# fmc.net
KiCad netlist of a schematic drawn in Altium Designer
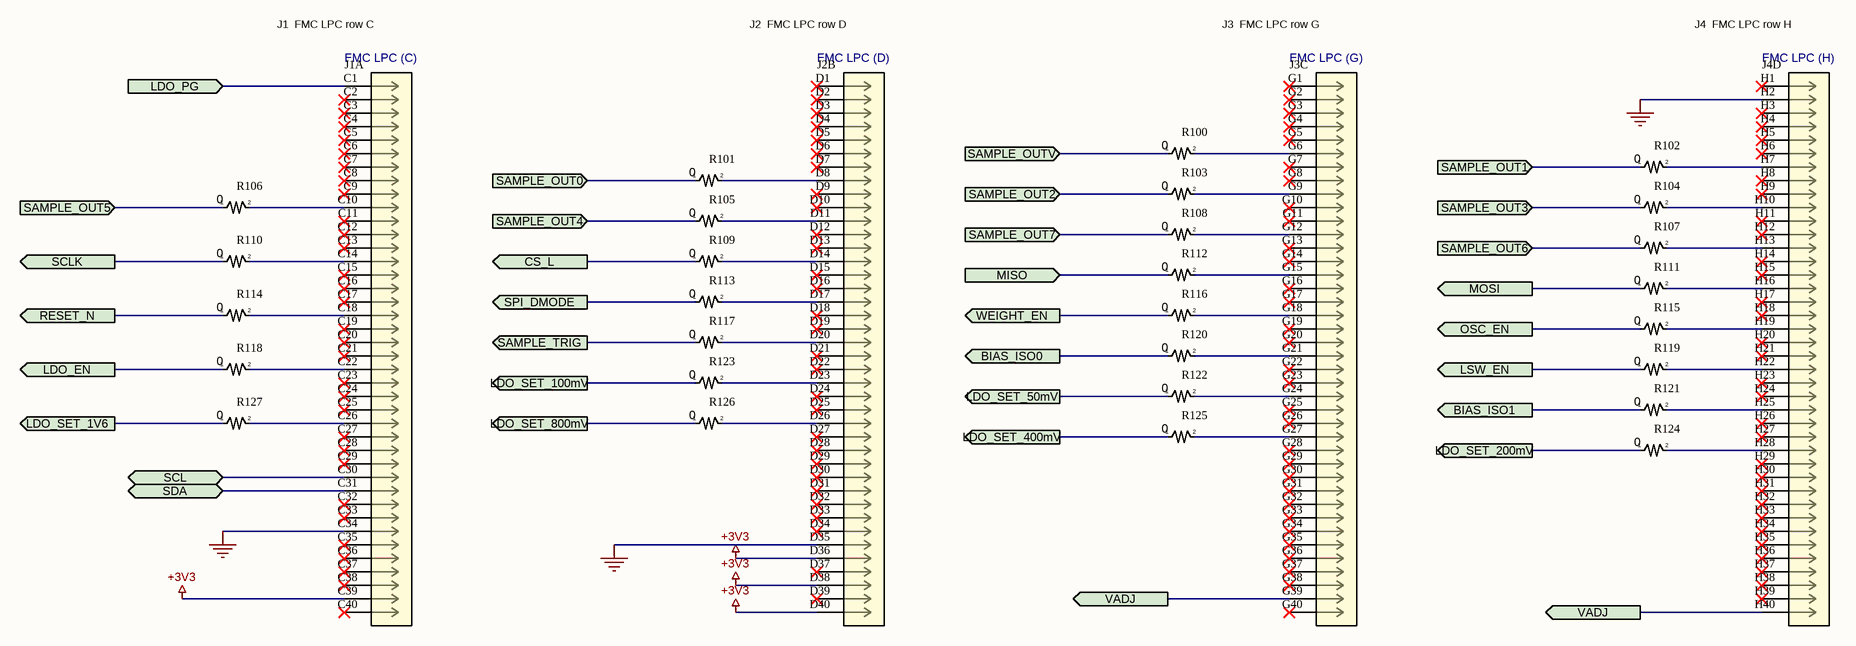
[diagram p0: fmc.SchDoc]

(export (version "E")
  (design (tool "Eeschema 10.0.6"))
  (components
    (comp (ref "J1")
      (value "FMC LPC (C)")
      (description "Description")
      (fields
        (field (name "MANUFACTURER_PART_NUMBER") "ASP-134606-01")
        (field (name "COPYRIGHT") "Copyright (C) 2025 Ultra Librarian. All rights reserved.")
      )
      (libsource (lib "parts") (part "ASP-134606-01"))
    )
    (comp (ref "J2")
      (value "FMC LPC (D)")
      (description "Description")
      (fields
        (field (name "MANUFACTURER_PART_NUMBER") "ASP-134606-01")
        (field (name "COPYRIGHT") "Copyright (C) 2025 Ultra Librarian. All rights reserved.")
      )
      (libsource (lib "") (part "ASP-134606-01_3"))
    )
    (comp (ref "J3")
      (value "FMC LPC (G)")
      (description "Description")
      (fields
        (field (name "MANUFACTURER_PART_NUMBER") "ASP-134606-01")
        (field (name "COPYRIGHT") "Copyright (C) 2025 Ultra Librarian. All rights reserved.")
      )
      (libsource (lib "") (part "ASP-134606-01_1"))
    )
    (comp (ref "J4")
      (value "FMC LPC (H)")
      (description "Description")
      (fields
        (field (name "MANUFACTURER_PART_NUMBER") "ASP-134606-01")
        (field (name "COPYRIGHT") "Copyright (C) 2025 Ultra Librarian. All rights reserved.")
      )
      (libsource (lib "") (part "ASP-134606-01_2"))
    )
    (comp (ref "R100")
      (value "0")
      (description "D10/CRCW0402 0R0 ET7 e3")
      (fields (field (name "MANUFACTURER_PART_NUMBER") "CRCW04020000Z0ED"))
      (libsource (lib "parts") (part "CRCW04020000Z0ED"))
    )
    (comp (ref "R101")
      (value "0")
      (description "D10/CRCW0402 0R0 ET7 e3")
      (fields (field (name "MANUFACTURER_PART_NUMBER") "CRCW04020000Z0ED"))
      (libsource (lib "parts") (part "CRCW04020000Z0ED"))
    )
    (comp (ref "R102")
      (value "0")
      (description "D10/CRCW0402 0R0 ET7 e3")
      (fields (field (name "MANUFACTURER_PART_NUMBER") "CRCW04020000Z0ED"))
      (libsource (lib "parts") (part "CRCW04020000Z0ED"))
    )
    (comp (ref "R103")
      (value "0")
      (description "D10/CRCW0402 0R0 ET7 e3")
      (fields (field (name "MANUFACTURER_PART_NUMBER") "CRCW04020000Z0ED"))
      (libsource (lib "parts") (part "CRCW04020000Z0ED"))
    )
    (comp (ref "R104")
      (value "0")
      (description "D10/CRCW0402 0R0 ET7 e3")
      (fields (field (name "MANUFACTURER_PART_NUMBER") "CRCW04020000Z0ED"))
      (libsource (lib "parts") (part "CRCW04020000Z0ED"))
    )
    (comp (ref "R105")
      (value "0")
      (description "D10/CRCW0402 0R0 ET7 e3")
      (fields (field (name "MANUFACTURER_PART_NUMBER") "CRCW04020000Z0ED"))
      (libsource (lib "parts") (part "CRCW04020000Z0ED"))
    )
    (comp (ref "R106")
      (value "0")
      (description "D10/CRCW0402 0R0 ET7 e3")
      (fields (field (name "MANUFACTURER_PART_NUMBER") "CRCW04020000Z0ED"))
      (libsource (lib "parts") (part "CRCW04020000Z0ED"))
    )
    (comp (ref "R107")
      (value "0")
      (description "D10/CRCW0402 0R0 ET7 e3")
      (fields (field (name "MANUFACTURER_PART_NUMBER") "CRCW04020000Z0ED"))
      (libsource (lib "parts") (part "CRCW04020000Z0ED"))
    )
    (comp (ref "R108")
      (value "0")
      (description "D10/CRCW0402 0R0 ET7 e3")
      (fields (field (name "MANUFACTURER_PART_NUMBER") "CRCW04020000Z0ED"))
      (libsource (lib "parts") (part "CRCW04020000Z0ED"))
    )
    (comp (ref "R109")
      (value "0")
      (description "D10/CRCW0402 0R0 ET7 e3")
      (fields (field (name "MANUFACTURER_PART_NUMBER") "CRCW04020000Z0ED"))
      (libsource (lib "parts") (part "CRCW04020000Z0ED"))
    )
    (comp (ref "R110")
      (value "0")
      (description "D10/CRCW0402 0R0 ET7 e3")
      (fields (field (name "MANUFACTURER_PART_NUMBER") "CRCW04020000Z0ED"))
      (libsource (lib "parts") (part "CRCW04020000Z0ED"))
    )
    (comp (ref "R111")
      (value "0")
      (description "D10/CRCW0402 0R0 ET7 e3")
      (fields (field (name "MANUFACTURER_PART_NUMBER") "CRCW04020000Z0ED"))
      (libsource (lib "parts") (part "CRCW04020000Z0ED"))
    )
    (comp (ref "R112")
      (value "0")
      (description "D10/CRCW0402 0R0 ET7 e3")
      (fields (field (name "MANUFACTURER_PART_NUMBER") "CRCW04020000Z0ED"))
      (libsource (lib "parts") (part "CRCW04020000Z0ED"))
    )
    (comp (ref "R113")
      (value "0")
      (description "D10/CRCW0402 0R0 ET7 e3")
      (fields (field (name "MANUFACTURER_PART_NUMBER") "CRCW04020000Z0ED"))
      (libsource (lib "parts") (part "CRCW04020000Z0ED"))
    )
    (comp (ref "R114")
      (value "0")
      (description "D10/CRCW0402 0R0 ET7 e3")
      (fields (field (name "MANUFACTURER_PART_NUMBER") "CRCW04020000Z0ED"))
      (libsource (lib "parts") (part "CRCW04020000Z0ED"))
    )
    (comp (ref "R115")
      (value "0")
      (description "D10/CRCW0402 0R0 ET7 e3")
      (fields (field (name "MANUFACTURER_PART_NUMBER") "CRCW04020000Z0ED"))
      (libsource (lib "parts") (part "CRCW04020000Z0ED"))
    )
    (comp (ref "R116")
      (value "0")
      (description "D10/CRCW0402 0R0 ET7 e3")
      (fields (field (name "MANUFACTURER_PART_NUMBER") "CRCW04020000Z0ED"))
      (libsource (lib "parts") (part "CRCW04020000Z0ED"))
    )
    (comp (ref "R117")
      (value "0")
      (description "D10/CRCW0402 0R0 ET7 e3")
      (fields (field (name "MANUFACTURER_PART_NUMBER") "CRCW04020000Z0ED"))
      (libsource (lib "parts") (part "CRCW04020000Z0ED"))
    )
    (comp (ref "R118")
      (value "0")
      (description "D10/CRCW0402 0R0 ET7 e3")
      (fields (field (name "MANUFACTURER_PART_NUMBER") "CRCW04020000Z0ED"))
      (libsource (lib "parts") (part "CRCW04020000Z0ED"))
    )
    (comp (ref "R119")
      (value "0")
      (description "D10/CRCW0402 0R0 ET7 e3")
      (fields (field (name "MANUFACTURER_PART_NUMBER") "CRCW04020000Z0ED"))
      (libsource (lib "parts") (part "CRCW04020000Z0ED"))
    )
    (comp (ref "R120")
      (value "0")
      (description "D10/CRCW0402 0R0 ET7 e3")
      (fields (field (name "MANUFACTURER_PART_NUMBER") "CRCW04020000Z0ED"))
      (libsource (lib "parts") (part "CRCW04020000Z0ED"))
    )
    (comp (ref "R121")
      (value "0")
      (description "D10/CRCW0402 0R0 ET7 e3")
      (fields (field (name "MANUFACTURER_PART_NUMBER") "CRCW04020000Z0ED"))
      (libsource (lib "parts") (part "CRCW04020000Z0ED"))
    )
    (comp (ref "R122")
      (value "0")
      (description "D10/CRCW0402 0R0 ET7 e3")
      (fields (field (name "MANUFACTURER_PART_NUMBER") "CRCW04020000Z0ED"))
      (libsource (lib "parts") (part "CRCW04020000Z0ED"))
    )
    (comp (ref "R123")
      (value "0")
      (description "D10/CRCW0402 0R0 ET7 e3")
      (fields (field (name "MANUFACTURER_PART_NUMBER") "CRCW04020000Z0ED"))
      (libsource (lib "parts") (part "CRCW04020000Z0ED"))
    )
    (comp (ref "R124")
      (value "0")
      (description "D10/CRCW0402 0R0 ET7 e3")
      (fields (field (name "MANUFACTURER_PART_NUMBER") "CRCW04020000Z0ED"))
      (libsource (lib "parts") (part "CRCW04020000Z0ED"))
    )
    (comp (ref "R125")
      (value "0")
      (description "D10/CRCW0402 0R0 ET7 e3")
      (fields (field (name "MANUFACTURER_PART_NUMBER") "CRCW04020000Z0ED"))
      (libsource (lib "parts") (part "CRCW04020000Z0ED"))
    )
    (comp (ref "R126")
      (value "0")
      (description "D10/CRCW0402 0R0 ET7 e3")
      (fields (field (name "MANUFACTURER_PART_NUMBER") "CRCW04020000Z0ED"))
      (libsource (lib "parts") (part "CRCW04020000Z0ED"))
    )
    (comp (ref "R127")
      (value "0")
      (description "D10/CRCW0402 0R0 ET7 e3")
      (fields (field (name "MANUFACTURER_PART_NUMBER") "CRCW04020000Z0ED"))
      (libsource (lib "parts") (part "CRCW04020000Z0ED"))
    )
  )
  (nets
    (net (code "1") (name "+3V3") (class "Default")
      (node (ref "J1") (pin "C39") (pinfunction "C39_C39") (pintype "passive"))
      (node (ref "J2") (pin "D36") (pinfunction "D36_D36") (pintype "passive"))
      (node (ref "J2") (pin "D38") (pinfunction "D38_D38") (pintype "passive"))
      (node (ref "J2") (pin "D40") (pinfunction "D40_D40") (pintype "passive"))
    )
    (net (code "2") (name "/BIAS_ISO0") (class "Default") (node (ref "R120") (pin "1") (pintype "passive")))
    (net (code "3") (name "/BIAS_ISO1") (class "Default") (node (ref "R121") (pin "1") (pintype "passive")))
    (net (code "4") (name "/CS_L") (class "Default") (node (ref "R109") (pin "1") (pintype "passive")))
    (net (code "5") (name "/LDO_EN") (class "Default") (node (ref "R118") (pin "1") (pintype "passive")))
    (net (code "6") (name "/LDO_PG") (class "Default")
      (node (ref "J1") (pin "C1") (pinfunction "C1_C1") (pintype "passive"))
    )
    (net (code "7") (name "/LDO_SET_1V6") (class "Default") (node (ref "R127") (pin "1") (pintype "passive")))
    (net (code "8") (name "/LDO_SET_50mV") (class "Default")
      (node (ref "R122") (pin "1") (pintype "passive"))
    )
    (net (code "9") (name "/LDO_SET_100mV") (class "Default")
      (node (ref "R123") (pin "1") (pintype "passive"))
    )
    (net (code "10") (name "/LDO_SET_200mV") (class "Default")
      (node (ref "R124") (pin "1") (pintype "passive"))
    )
    (net (code "11") (name "/LDO_SET_400mV") (class "Default")
      (node (ref "R125") (pin "1") (pintype "passive"))
    )
    (net (code "12") (name "/LDO_SET_800mV") (class "Default")
      (node (ref "R126") (pin "1") (pintype "passive"))
    )
    (net (code "13") (name "/LSW_EN") (class "Default") (node (ref "R119") (pin "1") (pintype "passive")))
    (net (code "14") (name "/MISO") (class "Default") (node (ref "R112") (pin "1") (pintype "passive")))
    (net (code "15") (name "/MOSI") (class "Default") (node (ref "R111") (pin "1") (pintype "passive")))
    (net (code "16") (name "/OSC_EN") (class "Default") (node (ref "R115") (pin "1") (pintype "passive")))
    (net (code "17") (name "/RESET_N") (class "Default") (node (ref "R114") (pin "1") (pintype "passive")))
    (net (code "18") (name "/SAMPLE_OUT0") (class "Default")
      (node (ref "R101") (pin "1") (pintype "passive"))
    )
    (net (code "19") (name "/SAMPLE_OUT1") (class "Default")
      (node (ref "R102") (pin "1") (pintype "passive"))
    )
    (net (code "20") (name "/SAMPLE_OUT2") (class "Default")
      (node (ref "R103") (pin "1") (pintype "passive"))
    )
    (net (code "21") (name "/SAMPLE_OUT3") (class "Default")
      (node (ref "R104") (pin "1") (pintype "passive"))
    )
    (net (code "22") (name "/SAMPLE_OUT4") (class "Default")
      (node (ref "R105") (pin "1") (pintype "passive"))
    )
    (net (code "23") (name "/SAMPLE_OUT5") (class "Default")
      (node (ref "R106") (pin "1") (pintype "passive"))
    )
    (net (code "24") (name "/SAMPLE_OUT6") (class "Default")
      (node (ref "R107") (pin "1") (pintype "passive"))
    )
    (net (code "25") (name "/SAMPLE_OUT7") (class "Default")
      (node (ref "R108") (pin "1") (pintype "passive"))
    )
    (net (code "26") (name "/SAMPLE_OUTV") (class "Default")
      (node (ref "R100") (pin "1") (pintype "passive"))
    )
    (net (code "27") (name "/SAMPLE_TRIG") (class "Default")
      (node (ref "R117") (pin "1") (pintype "passive"))
    )
    (net (code "28") (name "/SCL") (class "Default")
      (node (ref "J1") (pin "C30") (pinfunction "C30_C30") (pintype "passive"))
    )
    (net (code "29") (name "/SCLK") (class "Default") (node (ref "R110") (pin "1") (pintype "passive")))
    (net (code "30") (name "/SDA") (class "Default")
      (node (ref "J1") (pin "C31") (pinfunction "C31_C31") (pintype "passive"))
    )
    (net (code "31") (name "/SPI_DMODE") (class "Default") (node (ref "R113") (pin "1") (pintype "passive")))
    (net (code "32") (name "/VADJ") (class "Default")
      (node (ref "J3") (pin "G39") (pinfunction "G39_G39") (pintype "passive"))
      (node (ref "J4") (pin "H40") (pinfunction "H40_H40") (pintype "passive"))
    )
    (net (code "33") (name "/WEIGHT_EN") (class "Default") (node (ref "R116") (pin "1") (pintype "passive")))
    (net (code "34") (name "GND") (class "Default")
      (node (ref "J1") (pin "C34") (pinfunction "C34_C34") (pintype "passive"))
      (node (ref "J2") (pin "D35") (pinfunction "D35_D35") (pintype "passive"))
      (node (ref "J4") (pin "H2") (pinfunction "H2_H2") (pintype "passive"))
    )
    (net (code "35") (name "Net-(J1-PadC10)") (class "Default")
      (node (ref "J1") (pin "C10") (pinfunction "C10_C10") (pintype "passive"))
      (node (ref "R106") (pin "2") (pintype "passive"))
    )
    (net (code "36") (name "Net-(J1-PadC14)") (class "Default")
      (node (ref "J1") (pin "C14") (pinfunction "C14_C14") (pintype "passive"))
      (node (ref "R110") (pin "2") (pintype "passive"))
    )
    (net (code "37") (name "Net-(J1-PadC18)") (class "Default")
      (node (ref "J1") (pin "C18") (pinfunction "C18_C18") (pintype "passive"))
      (node (ref "R114") (pin "2") (pintype "passive"))
    )
    (net (code "38") (name "Net-(J1-PadC22)") (class "Default")
      (node (ref "J1") (pin "C22") (pinfunction "C22_C22") (pintype "passive"))
      (node (ref "R118") (pin "2") (pintype "passive"))
    )
    (net (code "39") (name "Net-(J1-PadC26)") (class "Default")
      (node (ref "J1") (pin "C26") (pinfunction "C26_C26") (pintype "passive"))
      (node (ref "R127") (pin "2") (pintype "passive"))
    )
    (net (code "40") (name "Net-(J2-PadD8)") (class "Default")
      (node (ref "J2") (pin "D8") (pinfunction "D8_D8") (pintype "passive"))
      (node (ref "R101") (pin "2") (pintype "passive"))
    )
    (net (code "41") (name "Net-(J2-PadD11)") (class "Default")
      (node (ref "J2") (pin "D11") (pinfunction "D11_D11") (pintype "passive"))
      (node (ref "R105") (pin "2") (pintype "passive"))
    )
    (net (code "42") (name "Net-(J2-PadD14)") (class "Default")
      (node (ref "J2") (pin "D14") (pinfunction "D14_D14") (pintype "passive"))
      (node (ref "R109") (pin "2") (pintype "passive"))
    )
    (net (code "43") (name "Net-(J2-PadD17)") (class "Default")
      (node (ref "J2") (pin "D17") (pinfunction "D17_D17") (pintype "passive"))
      (node (ref "R113") (pin "2") (pintype "passive"))
    )
    (net (code "44") (name "Net-(J2-PadD20)") (class "Default")
      (node (ref "J2") (pin "D20") (pinfunction "D20_D20") (pintype "passive"))
      (node (ref "R117") (pin "2") (pintype "passive"))
    )
    (net (code "45") (name "Net-(J2-PadD23)") (class "Default")
      (node (ref "J2") (pin "D23") (pinfunction "D23_D23") (pintype "passive"))
      (node (ref "R123") (pin "2") (pintype "passive"))
    )
    (net (code "46") (name "Net-(J2-PadD26)") (class "Default")
      (node (ref "J2") (pin "D26") (pinfunction "D26_D26") (pintype "passive"))
      (node (ref "R126") (pin "2") (pintype "passive"))
    )
    (net (code "47") (name "Net-(J3-PadG6)") (class "Default")
      (node (ref "J3") (pin "G6") (pinfunction "G6_G6") (pintype "passive"))
      (node (ref "R100") (pin "2") (pintype "passive"))
    )
    (net (code "48") (name "Net-(J3-PadG9)") (class "Default")
      (node (ref "J3") (pin "G9") (pinfunction "G9_G9") (pintype "passive"))
      (node (ref "R103") (pin "2") (pintype "passive"))
    )
    (net (code "49") (name "Net-(J3-PadG12)") (class "Default")
      (node (ref "J3") (pin "G12") (pinfunction "G12_G12") (pintype "passive"))
      (node (ref "R108") (pin "2") (pintype "passive"))
    )
    (net (code "50") (name "Net-(J3-PadG15)") (class "Default")
      (node (ref "J3") (pin "G15") (pinfunction "G15_G15") (pintype "passive"))
      (node (ref "R112") (pin "2") (pintype "passive"))
    )
    (net (code "51") (name "Net-(J3-PadG18)") (class "Default")
      (node (ref "J3") (pin "G18") (pinfunction "G18_G18") (pintype "passive"))
      (node (ref "R116") (pin "2") (pintype "passive"))
    )
    (net (code "52") (name "Net-(J3-PadG21)") (class "Default")
      (node (ref "J3") (pin "G21") (pinfunction "G21_G21") (pintype "passive"))
      (node (ref "R120") (pin "2") (pintype "passive"))
    )
    (net (code "53") (name "Net-(J3-PadG24)") (class "Default")
      (node (ref "J3") (pin "G24") (pinfunction "G24_G24") (pintype "passive"))
      (node (ref "R122") (pin "2") (pintype "passive"))
    )
    (net (code "54") (name "Net-(J3-PadG27)") (class "Default")
      (node (ref "J3") (pin "G27") (pinfunction "G27_G27") (pintype "passive"))
      (node (ref "R125") (pin "2") (pintype "passive"))
    )
    (net (code "55") (name "Net-(J4-PadH7)") (class "Default")
      (node (ref "J4") (pin "H7") (pinfunction "H7_H7") (pintype "passive"))
      (node (ref "R102") (pin "2") (pintype "passive"))
    )
    (net (code "56") (name "Net-(J4-PadH10)") (class "Default")
      (node (ref "J4") (pin "H10") (pinfunction "H10_H10") (pintype "passive"))
      (node (ref "R104") (pin "2") (pintype "passive"))
    )
    (net (code "57") (name "Net-(J4-PadH13)") (class "Default")
      (node (ref "J4") (pin "H13") (pinfunction "H13_H13") (pintype "passive"))
      (node (ref "R107") (pin "2") (pintype "passive"))
    )
    (net (code "58") (name "Net-(J4-PadH16)") (class "Default")
      (node (ref "J4") (pin "H16") (pinfunction "H16_H16") (pintype "passive"))
      (node (ref "R111") (pin "2") (pintype "passive"))
    )
    (net (code "59") (name "Net-(J4-PadH19)") (class "Default")
      (node (ref "J4") (pin "H19") (pinfunction "H19_H19") (pintype "passive"))
      (node (ref "R115") (pin "2") (pintype "passive"))
    )
    (net (code "60") (name "Net-(J4-PadH22)") (class "Default")
      (node (ref "J4") (pin "H22") (pinfunction "H22_H22") (pintype "passive"))
      (node (ref "R119") (pin "2") (pintype "passive"))
    )
    (net (code "61") (name "Net-(J4-PadH25)") (class "Default")
      (node (ref "J4") (pin "H25") (pinfunction "H25_H25") (pintype "passive"))
      (node (ref "R121") (pin "2") (pintype "passive"))
    )
    (net (code "62") (name "Net-(J4-PadH28)") (class "Default")
      (node (ref "J4") (pin "H28") (pinfunction "H28_H28") (pintype "passive"))
      (node (ref "R124") (pin "2") (pintype "passive"))
    )
    (net (code "63") (name "unconnected-(J1-PadC2)") (class "Default")
      (node (ref "J1") (pin "C2") (pinfunction "C2_C2") (pintype "passive+no_connect"))
    )
    (net (code "64") (name "unconnected-(J1-PadC3)") (class "Default")
      (node (ref "J1") (pin "C3") (pinfunction "C3_C3") (pintype "passive+no_connect"))
    )
    (net (code "65") (name "unconnected-(J1-PadC4)") (class "Default")
      (node (ref "J1") (pin "C4") (pinfunction "C4_C4") (pintype "passive+no_connect"))
    )
    (net (code "66") (name "unconnected-(J1-PadC5)") (class "Default")
      (node (ref "J1") (pin "C5") (pinfunction "C5_C5") (pintype "passive+no_connect"))
    )
    (net (code "67") (name "unconnected-(J1-PadC6)") (class "Default")
      (node (ref "J1") (pin "C6") (pinfunction "C6_C6") (pintype "passive+no_connect"))
    )
    (net (code "68") (name "unconnected-(J1-PadC7)") (class "Default")
      (node (ref "J1") (pin "C7") (pinfunction "C7_C7") (pintype "passive+no_connect"))
    )
    (net (code "69") (name "unconnected-(J1-PadC8)") (class "Default")
      (node (ref "J1") (pin "C8") (pinfunction "C8_C8") (pintype "passive+no_connect"))
    )
    (net (code "70") (name "unconnected-(J1-PadC9)") (class "Default")
      (node (ref "J1") (pin "C9") (pinfunction "C9_C9") (pintype "passive+no_connect"))
    )
    (net (code "71") (name "unconnected-(J1-PadC11)") (class "Default")
      (node (ref "J1") (pin "C11") (pinfunction "C11_C11") (pintype "passive+no_connect"))
    )
    (net (code "72") (name "unconnected-(J1-PadC12)") (class "Default")
      (node (ref "J1") (pin "C12") (pinfunction "C12_C12") (pintype "passive+no_connect"))
    )
    (net (code "73") (name "unconnected-(J1-PadC13)") (class "Default")
      (node (ref "J1") (pin "C13") (pinfunction "C13_C13") (pintype "passive+no_connect"))
    )
    (net (code "74") (name "unconnected-(J1-PadC15)") (class "Default")
      (node (ref "J1") (pin "C15") (pinfunction "C15_C15") (pintype "passive+no_connect"))
    )
    (net (code "75") (name "unconnected-(J1-PadC16)") (class "Default")
      (node (ref "J1") (pin "C16") (pinfunction "C16_C16") (pintype "passive+no_connect"))
    )
    (net (code "76") (name "unconnected-(J1-PadC17)") (class "Default")
      (node (ref "J1") (pin "C17") (pinfunction "C17_C17") (pintype "passive+no_connect"))
    )
    (net (code "77") (name "unconnected-(J1-PadC19)") (class "Default")
      (node (ref "J1") (pin "C19") (pinfunction "C19_C19") (pintype "passive+no_connect"))
    )
    (net (code "78") (name "unconnected-(J1-PadC20)") (class "Default")
      (node (ref "J1") (pin "C20") (pinfunction "C20_C20") (pintype "passive+no_connect"))
    )
    (net (code "79") (name "unconnected-(J1-PadC21)") (class "Default")
      (node (ref "J1") (pin "C21") (pinfunction "C21_C21") (pintype "passive+no_connect"))
    )
    (net (code "80") (name "unconnected-(J1-PadC23)") (class "Default")
      (node (ref "J1") (pin "C23") (pinfunction "C23_C23") (pintype "passive+no_connect"))
    )
    (net (code "81") (name "unconnected-(J1-PadC24)") (class "Default")
      (node (ref "J1") (pin "C24") (pinfunction "C24_C24") (pintype "passive+no_connect"))
    )
    (net (code "82") (name "unconnected-(J1-PadC25)") (class "Default")
      (node (ref "J1") (pin "C25") (pinfunction "C25_C25") (pintype "passive+no_connect"))
    )
    (net (code "83") (name "unconnected-(J1-PadC27)") (class "Default")
      (node (ref "J1") (pin "C27") (pinfunction "C27_C27") (pintype "passive+no_connect"))
    )
    (net (code "84") (name "unconnected-(J1-PadC28)") (class "Default")
      (node (ref "J1") (pin "C28") (pinfunction "C28_C28") (pintype "passive+no_connect"))
    )
    (net (code "85") (name "unconnected-(J1-PadC29)") (class "Default")
      (node (ref "J1") (pin "C29") (pinfunction "C29_C29") (pintype "passive+no_connect"))
    )
    (net (code "86") (name "unconnected-(J1-PadC32)") (class "Default")
      (node (ref "J1") (pin "C32") (pinfunction "C32_C32") (pintype "passive+no_connect"))
    )
    (net (code "87") (name "unconnected-(J1-PadC33)") (class "Default")
      (node (ref "J1") (pin "C33") (pinfunction "C33_C33") (pintype "passive+no_connect"))
    )
    (net (code "88") (name "unconnected-(J1-PadC35)") (class "Default")
      (node (ref "J1") (pin "C35") (pinfunction "C35_C35") (pintype "passive+no_connect"))
    )
    (net (code "89") (name "unconnected-(J1-PadC36)") (class "Default")
      (node (ref "J1") (pin "C36") (pinfunction "C36_C36") (pintype "passive+no_connect"))
    )
    (net (code "90") (name "unconnected-(J1-PadC37)") (class "Default")
      (node (ref "J1") (pin "C37") (pinfunction "C37_C37") (pintype "passive+no_connect"))
    )
    (net (code "91") (name "unconnected-(J1-PadC38)") (class "Default")
      (node (ref "J1") (pin "C38") (pinfunction "C38_C38") (pintype "passive+no_connect"))
    )
    (net (code "92") (name "unconnected-(J1-PadC40)") (class "Default")
      (node (ref "J1") (pin "C40") (pinfunction "C40_C40") (pintype "passive+no_connect"))
    )
    (net (code "93") (name "unconnected-(J2-PadD1)") (class "Default")
      (node (ref "J2") (pin "D1") (pinfunction "D1_D1") (pintype "passive+no_connect"))
    )
    (net (code "94") (name "unconnected-(J2-PadD2)") (class "Default")
      (node (ref "J2") (pin "D2") (pinfunction "D2_D2") (pintype "passive+no_connect"))
    )
    (net (code "95") (name "unconnected-(J2-PadD3)") (class "Default")
      (node (ref "J2") (pin "D3") (pinfunction "D3_D3") (pintype "passive+no_connect"))
    )
    (net (code "96") (name "unconnected-(J2-PadD4)") (class "Default")
      (node (ref "J2") (pin "D4") (pinfunction "D4_D4") (pintype "passive+no_connect"))
    )
    (net (code "97") (name "unconnected-(J2-PadD5)") (class "Default")
      (node (ref "J2") (pin "D5") (pinfunction "D5_D5") (pintype "passive+no_connect"))
    )
    (net (code "98") (name "unconnected-(J2-PadD6)") (class "Default")
      (node (ref "J2") (pin "D6") (pinfunction "D6_D6") (pintype "passive+no_connect"))
    )
    (net (code "99") (name "unconnected-(J2-PadD7)") (class "Default")
      (node (ref "J2") (pin "D7") (pinfunction "D7_D7") (pintype "passive+no_connect"))
    )
    (net (code "100") (name "unconnected-(J2-PadD9)") (class "Default")
      (node (ref "J2") (pin "D9") (pinfunction "D9_D9") (pintype "passive+no_connect"))
    )
    (net (code "101") (name "unconnected-(J2-PadD10)") (class "Default")
      (node (ref "J2") (pin "D10") (pinfunction "D10_D10") (pintype "passive+no_connect"))
    )
    (net (code "102") (name "unconnected-(J2-PadD12)") (class "Default")
      (node (ref "J2") (pin "D12") (pinfunction "D12_D12") (pintype "passive+no_connect"))
    )
    (net (code "103") (name "unconnected-(J2-PadD13)") (class "Default")
      (node (ref "J2") (pin "D13") (pinfunction "D13_D13") (pintype "passive+no_connect"))
    )
    (net (code "104") (name "unconnected-(J2-PadD15)") (class "Default")
      (node (ref "J2") (pin "D15") (pinfunction "D15_D15") (pintype "passive+no_connect"))
    )
    (net (code "105") (name "unconnected-(J2-PadD16)") (class "Default")
      (node (ref "J2") (pin "D16") (pinfunction "D16_D16") (pintype "passive+no_connect"))
    )
    (net (code "106") (name "unconnected-(J2-PadD18)") (class "Default")
      (node (ref "J2") (pin "D18") (pinfunction "D18_D18") (pintype "passive+no_connect"))
    )
    (net (code "107") (name "unconnected-(J2-PadD19)") (class "Default")
      (node (ref "J2") (pin "D19") (pinfunction "D19_D19") (pintype "passive+no_connect"))
    )
    (net (code "108") (name "unconnected-(J2-PadD21)") (class "Default")
      (node (ref "J2") (pin "D21") (pinfunction "D21_D21") (pintype "passive+no_connect"))
    )
    (net (code "109") (name "unconnected-(J2-PadD22)") (class "Default")
      (node (ref "J2") (pin "D22") (pinfunction "D22_D22") (pintype "passive+no_connect"))
    )
    (net (code "110") (name "unconnected-(J2-PadD24)") (class "Default")
      (node (ref "J2") (pin "D24") (pinfunction "D24_D24") (pintype "passive+no_connect"))
    )
    (net (code "111") (name "unconnected-(J2-PadD25)") (class "Default")
      (node (ref "J2") (pin "D25") (pinfunction "D25_D25") (pintype "passive+no_connect"))
    )
    (net (code "112") (name "unconnected-(J2-PadD27)") (class "Default")
      (node (ref "J2") (pin "D27") (pinfunction "D27_D27") (pintype "passive+no_connect"))
    )
    (net (code "113") (name "unconnected-(J2-PadD28)") (class "Default")
      (node (ref "J2") (pin "D28") (pinfunction "D28_D28") (pintype "passive+no_connect"))
    )
    (net (code "114") (name "unconnected-(J2-PadD29)") (class "Default")
      (node (ref "J2") (pin "D29") (pinfunction "D29_D29") (pintype "passive+no_connect"))
    )
    (net (code "115") (name "unconnected-(J2-PadD30)") (class "Default")
      (node (ref "J2") (pin "D30") (pinfunction "D30_D30") (pintype "passive+no_connect"))
    )
    (net (code "116") (name "unconnected-(J2-PadD31)") (class "Default")
      (node (ref "J2") (pin "D31") (pinfunction "D31_D31") (pintype "passive+no_connect"))
    )
    (net (code "117") (name "unconnected-(J2-PadD32)") (class "Default")
      (node (ref "J2") (pin "D32") (pinfunction "D32_D32") (pintype "passive+no_connect"))
    )
    (net (code "118") (name "unconnected-(J2-PadD33)") (class "Default")
      (node (ref "J2") (pin "D33") (pinfunction "D33_D33") (pintype "passive+no_connect"))
    )
    (net (code "119") (name "unconnected-(J2-PadD34)") (class "Default")
      (node (ref "J2") (pin "D34") (pinfunction "D34_D34") (pintype "passive+no_connect"))
    )
    (net (code "120") (name "unconnected-(J2-PadD37)") (class "Default")
      (node (ref "J2") (pin "D37") (pinfunction "D37_D37") (pintype "passive+no_connect"))
    )
    (net (code "121") (name "unconnected-(J2-PadD39)") (class "Default")
      (node (ref "J2") (pin "D39") (pinfunction "D39_D39") (pintype "passive+no_connect"))
    )
    (net (code "122") (name "unconnected-(J3-PadG1)") (class "Default")
      (node (ref "J3") (pin "G1") (pinfunction "G1_G1") (pintype "passive+no_connect"))
    )
    (net (code "123") (name "unconnected-(J3-PadG2)") (class "Default")
      (node (ref "J3") (pin "G2") (pinfunction "G2_G2") (pintype "passive+no_connect"))
    )
    (net (code "124") (name "unconnected-(J3-PadG3)") (class "Default")
      (node (ref "J3") (pin "G3") (pinfunction "G3_G3") (pintype "passive+no_connect"))
    )
    (net (code "125") (name "unconnected-(J3-PadG4)") (class "Default")
      (node (ref "J3") (pin "G4") (pinfunction "G4_G4") (pintype "passive+no_connect"))
    )
    (net (code "126") (name "unconnected-(J3-PadG5)") (class "Default")
      (node (ref "J3") (pin "G5") (pinfunction "G5_G5") (pintype "passive+no_connect"))
    )
    (net (code "127") (name "unconnected-(J3-PadG7)") (class "Default")
      (node (ref "J3") (pin "G7") (pinfunction "G7_G7") (pintype "passive+no_connect"))
    )
    (net (code "128") (name "unconnected-(J3-PadG8)") (class "Default")
      (node (ref "J3") (pin "G8") (pinfunction "G8_G8") (pintype "passive+no_connect"))
    )
    (net (code "129") (name "unconnected-(J3-PadG10)") (class "Default")
      (node (ref "J3") (pin "G10") (pinfunction "G10_G10") (pintype "passive+no_connect"))
    )
    (net (code "130") (name "unconnected-(J3-PadG11)") (class "Default")
      (node (ref "J3") (pin "G11") (pinfunction "G11_G11") (pintype "passive+no_connect"))
    )
    (net (code "131") (name "unconnected-(J3-PadG13)") (class "Default")
      (node (ref "J3") (pin "G13") (pinfunction "G13_G13") (pintype "passive+no_connect"))
    )
    (net (code "132") (name "unconnected-(J3-PadG14)") (class "Default")
      (node (ref "J3") (pin "G14") (pinfunction "G14_G14") (pintype "passive+no_connect"))
    )
    (net (code "133") (name "unconnected-(J3-PadG16)") (class "Default")
      (node (ref "J3") (pin "G16") (pinfunction "G16_G16") (pintype "passive+no_connect"))
    )
    (net (code "134") (name "unconnected-(J3-PadG17)") (class "Default")
      (node (ref "J3") (pin "G17") (pinfunction "G17_G17") (pintype "passive+no_connect"))
    )
    (net (code "135") (name "unconnected-(J3-PadG19)") (class "Default")
      (node (ref "J3") (pin "G19") (pinfunction "G19_G19") (pintype "passive+no_connect"))
    )
    (net (code "136") (name "unconnected-(J3-PadG20)") (class "Default")
      (node (ref "J3") (pin "G20") (pinfunction "G20_G20") (pintype "passive+no_connect"))
    )
    (net (code "137") (name "unconnected-(J3-PadG22)") (class "Default")
      (node (ref "J3") (pin "G22") (pinfunction "G22_G22") (pintype "passive+no_connect"))
    )
    (net (code "138") (name "unconnected-(J3-PadG23)") (class "Default")
      (node (ref "J3") (pin "G23") (pinfunction "G23_G23") (pintype "passive+no_connect"))
    )
    (net (code "139") (name "unconnected-(J3-PadG25)") (class "Default")
      (node (ref "J3") (pin "G25") (pinfunction "G25_G25") (pintype "passive+no_connect"))
    )
    (net (code "140") (name "unconnected-(J3-PadG26)") (class "Default")
      (node (ref "J3") (pin "G26") (pinfunction "G26_G26") (pintype "passive+no_connect"))
    )
    (net (code "141") (name "unconnected-(J3-PadG28)") (class "Default")
      (node (ref "J3") (pin "G28") (pinfunction "G28_G28") (pintype "passive+no_connect"))
    )
    (net (code "142") (name "unconnected-(J3-PadG29)") (class "Default")
      (node (ref "J3") (pin "G29") (pinfunction "G29_G29") (pintype "passive+no_connect"))
    )
    (net (code "143") (name "unconnected-(J3-PadG30)") (class "Default")
      (node (ref "J3") (pin "G30") (pinfunction "G30_G30") (pintype "passive+no_connect"))
    )
    (net (code "144") (name "unconnected-(J3-PadG31)") (class "Default")
      (node (ref "J3") (pin "G31") (pinfunction "G31_G31") (pintype "passive+no_connect"))
    )
    (net (code "145") (name "unconnected-(J3-PadG32)") (class "Default")
      (node (ref "J3") (pin "G32") (pinfunction "G32_G32") (pintype "passive+no_connect"))
    )
    (net (code "146") (name "unconnected-(J3-PadG33)") (class "Default")
      (node (ref "J3") (pin "G33") (pinfunction "G33_G33") (pintype "passive+no_connect"))
    )
    (net (code "147") (name "unconnected-(J3-PadG34)") (class "Default")
      (node (ref "J3") (pin "G34") (pinfunction "G34_G34") (pintype "passive+no_connect"))
    )
    (net (code "148") (name "unconnected-(J3-PadG35)") (class "Default")
      (node (ref "J3") (pin "G35") (pinfunction "G35_G35") (pintype "passive+no_connect"))
    )
    (net (code "149") (name "unconnected-(J3-PadG36)") (class "Default")
      (node (ref "J3") (pin "G36") (pinfunction "G36_G36") (pintype "passive+no_connect"))
    )
    (net (code "150") (name "unconnected-(J3-PadG37)") (class "Default")
      (node (ref "J3") (pin "G37") (pinfunction "G37_G37") (pintype "passive+no_connect"))
    )
    (net (code "151") (name "unconnected-(J3-PadG38)") (class "Default")
      (node (ref "J3") (pin "G38") (pinfunction "G38_G38") (pintype "passive+no_connect"))
    )
    (net (code "152") (name "unconnected-(J3-PadG40)") (class "Default")
      (node (ref "J3") (pin "G40") (pinfunction "G40_G40") (pintype "passive+no_connect"))
    )
    (net (code "153") (name "unconnected-(J4-PadH1)") (class "Default")
      (node (ref "J4") (pin "H1") (pinfunction "H1_H1") (pintype "passive+no_connect"))
    )
    (net (code "154") (name "unconnected-(J4-PadH3)") (class "Default")
      (node (ref "J4") (pin "H3") (pinfunction "H3_H3") (pintype "passive+no_connect"))
    )
    (net (code "155") (name "unconnected-(J4-PadH4)") (class "Default")
      (node (ref "J4") (pin "H4") (pinfunction "H4_H4") (pintype "passive+no_connect"))
    )
    (net (code "156") (name "unconnected-(J4-PadH5)") (class "Default")
      (node (ref "J4") (pin "H5") (pinfunction "H5_H5") (pintype "passive+no_connect"))
    )
    (net (code "157") (name "unconnected-(J4-PadH6)") (class "Default")
      (node (ref "J4") (pin "H6") (pinfunction "H6_H6") (pintype "passive+no_connect"))
    )
    (net (code "158") (name "unconnected-(J4-PadH8)") (class "Default")
      (node (ref "J4") (pin "H8") (pinfunction "H8_H8") (pintype "passive+no_connect"))
    )
    (net (code "159") (name "unconnected-(J4-PadH9)") (class "Default")
      (node (ref "J4") (pin "H9") (pinfunction "H9_H9") (pintype "passive+no_connect"))
    )
    (net (code "160") (name "unconnected-(J4-PadH11)") (class "Default")
      (node (ref "J4") (pin "H11") (pinfunction "H11_H11") (pintype "passive+no_connect"))
    )
    (net (code "161") (name "unconnected-(J4-PadH12)") (class "Default")
      (node (ref "J4") (pin "H12") (pinfunction "H12_H12") (pintype "passive+no_connect"))
    )
    (net (code "162") (name "unconnected-(J4-PadH14)") (class "Default")
      (node (ref "J4") (pin "H14") (pinfunction "H14_H14") (pintype "passive+no_connect"))
    )
    (net (code "163") (name "unconnected-(J4-PadH15)") (class "Default")
      (node (ref "J4") (pin "H15") (pinfunction "H15_H15") (pintype "passive+no_connect"))
    )
    (net (code "164") (name "unconnected-(J4-PadH17)") (class "Default")
      (node (ref "J4") (pin "H17") (pinfunction "H17_H17") (pintype "passive+no_connect"))
    )
    (net (code "165") (name "unconnected-(J4-PadH18)") (class "Default")
      (node (ref "J4") (pin "H18") (pinfunction "H18_H18") (pintype "passive+no_connect"))
    )
    (net (code "166") (name "unconnected-(J4-PadH20)") (class "Default")
      (node (ref "J4") (pin "H20") (pinfunction "H20_H20") (pintype "passive+no_connect"))
    )
    (net (code "167") (name "unconnected-(J4-PadH21)") (class "Default")
      (node (ref "J4") (pin "H21") (pinfunction "H21_H21") (pintype "passive+no_connect"))
    )
    (net (code "168") (name "unconnected-(J4-PadH23)") (class "Default")
      (node (ref "J4") (pin "H23") (pinfunction "H23_H23") (pintype "passive+no_connect"))
    )
    (net (code "169") (name "unconnected-(J4-PadH24)") (class "Default")
      (node (ref "J4") (pin "H24") (pinfunction "H24_H24") (pintype "passive+no_connect"))
    )
    (net (code "170") (name "unconnected-(J4-PadH26)") (class "Default")
      (node (ref "J4") (pin "H26") (pinfunction "H26_H26") (pintype "passive+no_connect"))
    )
    (net (code "171") (name "unconnected-(J4-PadH27)") (class "Default")
      (node (ref "J4") (pin "H27") (pinfunction "H27_H27") (pintype "passive+no_connect"))
    )
    (net (code "172") (name "unconnected-(J4-PadH29)") (class "Default")
      (node (ref "J4") (pin "H29") (pinfunction "H29_H29") (pintype "passive+no_connect"))
    )
    (net (code "173") (name "unconnected-(J4-PadH30)") (class "Default")
      (node (ref "J4") (pin "H30") (pinfunction "H30_H30") (pintype "passive+no_connect"))
    )
    (net (code "174") (name "unconnected-(J4-PadH31)") (class "Default")
      (node (ref "J4") (pin "H31") (pinfunction "H31_H31") (pintype "passive+no_connect"))
    )
    (net (code "175") (name "unconnected-(J4-PadH32)") (class "Default")
      (node (ref "J4") (pin "H32") (pinfunction "H32_H32") (pintype "passive+no_connect"))
    )
    (net (code "176") (name "unconnected-(J4-PadH33)") (class "Default")
      (node (ref "J4") (pin "H33") (pinfunction "H33_H33") (pintype "passive+no_connect"))
    )
    (net (code "177") (name "unconnected-(J4-PadH34)") (class "Default")
      (node (ref "J4") (pin "H34") (pinfunction "H34_H34") (pintype "passive+no_connect"))
    )
    (net (code "178") (name "unconnected-(J4-PadH35)") (class "Default")
      (node (ref "J4") (pin "H35") (pinfunction "H35_H35") (pintype "passive+no_connect"))
    )
    (net (code "179") (name "unconnected-(J4-PadH36)") (class "Default")
      (node (ref "J4") (pin "H36") (pinfunction "H36_H36") (pintype "passive+no_connect"))
    )
    (net (code "180") (name "unconnected-(J4-PadH37)") (class "Default")
      (node (ref "J4") (pin "H37") (pinfunction "H37_H37") (pintype "passive+no_connect"))
    )
    (net (code "181") (name "unconnected-(J4-PadH38)") (class "Default")
      (node (ref "J4") (pin "H38") (pinfunction "H38_H38") (pintype "passive+no_connect"))
    )
    (net (code "182") (name "unconnected-(J4-PadH39)") (class "Default")
      (node (ref "J4") (pin "H39") (pinfunction "H39_H39") (pintype "passive+no_connect"))
    )
  )
)
